# display.net
KiCad netlist of a schematic drawn in Altium Designer
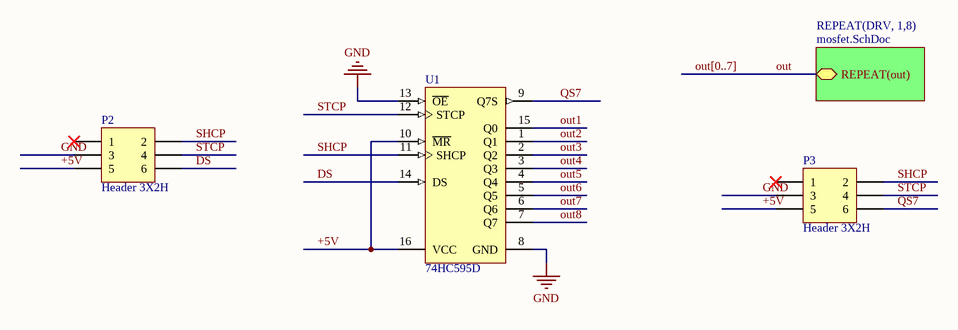
[diagram p0: display.SchDoc]

(export (version "E")
  (design (tool "Eeschema 10.0.6"))
  (components
    (comp (ref "P2")
      (value "Header 3X2H")
      (footprint "HDR2X3H")
      (description "Header, 3-Pin, Dual row, Right Angle")
      (fields (field (name "PUBLISHER") "Altium Limited"))
      (libsource (lib "Miscellaneous Connectors") (part "Header 3X2H"))
    )
    (comp (ref "P3")
      (value "Header 3X2H")
      (footprint "HDR2X3H")
      (description "Header, 3-Pin, Dual row, Right Angle")
      (fields (field (name "PUBLISHER") "Altium Limited"))
      (libsource (lib "Miscellaneous Connectors") (part "Header 3X2H"))
    )
    (comp (ref "U1")
      (value "74HC595D")
      (footprint "NXP-SOT109-1_V")
      (fields (field (name "MANUFACTURER") "NXP Semiconductors"))
      (libsource (lib "Altium Content Vault") (part "NXP-74HC595D-SOP-16"))
    )
  )
  (nets
    (net (code "2") (name "/+5V") (class "Default")
      (node (ref "P2") (pin "5") (pinfunction "5_5") (pintype "passive"))
      (node (ref "P3") (pin "5") (pinfunction "5_5") (pintype "passive"))
      (node (ref "U1") (pin "10") (pinfunction "~{MR}_10") (pintype "input"))
      (node (ref "U1") (pin "16") (pinfunction "VCC_16") (pintype "power_in"))
    )
    (net (code "3") (name "/DS") (class "Default")
      (node (ref "P2") (pin "6") (pinfunction "6_6") (pintype "passive"))
      (node (ref "U1") (pin "14") (pinfunction "DS_14") (pintype "input"))
    )
    (net (code "4") (name "/QS7") (class "Default")
      (node (ref "P3") (pin "6") (pinfunction "6_6") (pintype "passive"))
      (node (ref "U1") (pin "9") (pinfunction "Q7S_9") (pintype "output"))
    )
    (net (code "5") (name "/SHCP") (class "Default")
      (node (ref "P2") (pin "2") (pinfunction "2_2") (pintype "passive"))
      (node (ref "P3") (pin "2") (pinfunction "2_2") (pintype "passive"))
      (node (ref "U1") (pin "11") (pinfunction "SHCP_11") (pintype "input"))
    )
    (net (code "6") (name "/STCP") (class "Default")
      (node (ref "P2") (pin "4") (pinfunction "4_4") (pintype "passive"))
      (node (ref "P3") (pin "4") (pinfunction "4_4") (pintype "passive"))
      (node (ref "U1") (pin "12") (pinfunction "STCP_12") (pintype "input"))
    )
    (net (code "8") (name "/out1") (class "Default")
      (node (ref "U1") (pin "15") (pinfunction "Q0_15") (pintype "tri_state"))
    )
    (net (code "9") (name "/out2") (class "Default")
      (node (ref "U1") (pin "1") (pinfunction "Q1_1") (pintype "tri_state"))
    )
    (net (code "10") (name "/out3") (class "Default")
      (node (ref "U1") (pin "2") (pinfunction "Q2_2") (pintype "tri_state"))
    )
    (net (code "11") (name "/out4") (class "Default")
      (node (ref "U1") (pin "3") (pinfunction "Q3_3") (pintype "tri_state"))
    )
    (net (code "12") (name "/out5") (class "Default")
      (node (ref "U1") (pin "4") (pinfunction "Q4_4") (pintype "tri_state"))
    )
    (net (code "13") (name "/out6") (class "Default")
      (node (ref "U1") (pin "5") (pinfunction "Q5_5") (pintype "tri_state"))
    )
    (net (code "14") (name "/out7") (class "Default")
      (node (ref "U1") (pin "6") (pinfunction "Q6_6") (pintype "tri_state"))
    )
    (net (code "15") (name "/out8") (class "Default")
      (node (ref "U1") (pin "7") (pinfunction "Q7_7") (pintype "tri_state"))
    )
    (net (code "17") (name "GND") (class "Default")
      (node (ref "P2") (pin "3") (pinfunction "3_3") (pintype "passive"))
      (node (ref "P3") (pin "3") (pinfunction "3_3") (pintype "passive"))
      (node (ref "U1") (pin "13") (pinfunction "~{OE}_13") (pintype "input"))
      (node (ref "U1") (pin "8") (pinfunction "GND_8") (pintype "power_in"))
    )
    (net (code "18") (name "unconnected-(P2-Pad1)") (class "Default")
      (node (ref "P2") (pin "1") (pinfunction "1_1") (pintype "passive+no_connect"))
    )
    (net (code "19") (name "unconnected-(P3-Pad1)") (class "Default")
      (node (ref "P3") (pin "1") (pinfunction "1_1") (pintype "passive+no_connect"))
    )
  )
)
